# P08_eMMC.net
KiCad netlist of a schematic drawn in Altium Designer
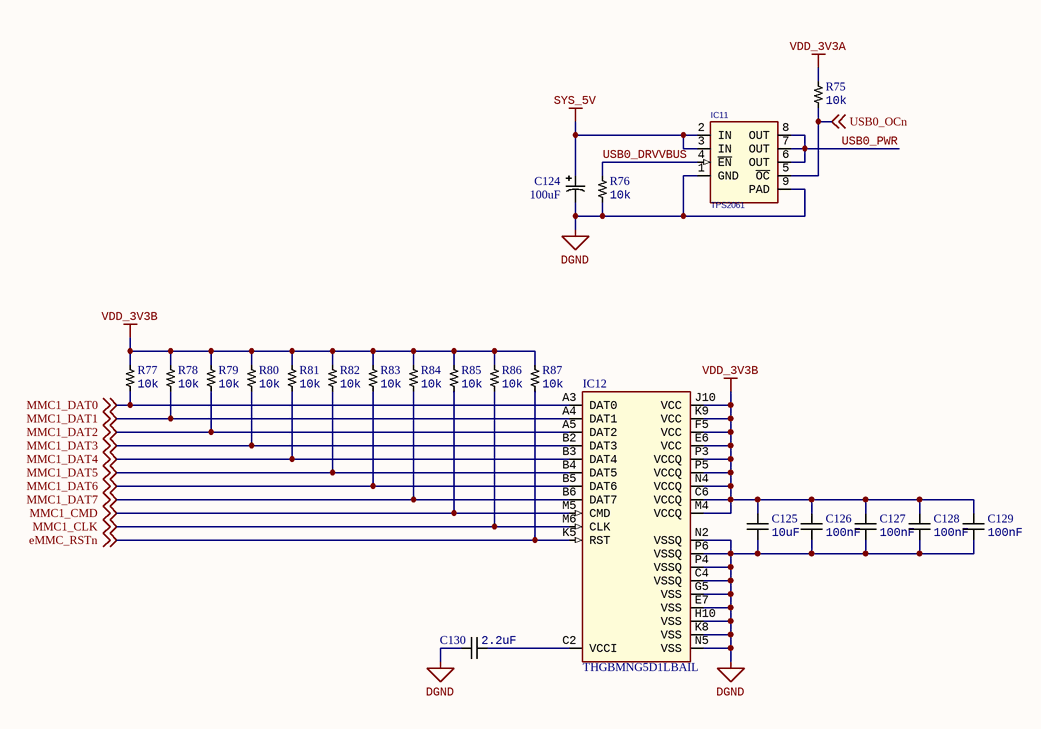
[diagram p0: P08_eMMC.SchDoc]

(export (version "E")
  (design (tool "Eeschema 10.0.6"))
  (components
    (comp (ref "C124")
      (value "EEE-0JA101SP")
      (footprint "Orient:CAP6.6x6.6")
      (description "POL CAP 100uF SMD")
      (fields
        (field (name "MANUFACTURER") "Panasonic")
        (field (name "TOLERANCE") "20%")
        (field (name "CAPACITANCE") "100uF")
      )
      (libsource (lib "Orient") (part "CAP_POL_100uF"))
    )
    (comp (ref "C125")
      (value "C2012X6S1A106K085AC")
      (footprint "Orient:CAP0805")
      (description "MLCC 10uF 0805 SMD")
      (fields
        (field (name "MANUFACTURER") "TDK")
        (field (name "CAPACITANCE") "10uF")
        (field (name "TOLERANCE") "10%")
      )
      (libsource (lib "Orient") (part "CAP_10uF"))
    )
    (comp (ref "C126")
      (value "C0402C104K4RACTU")
      (footprint "Orient:CAP0402")
      (description "MLCC 100nF 0402 SMD")
      (fields
        (field (name "MANUFACTURER") "KEMET")
        (field (name "TOLERANCE") "10%")
        (field (name "CAPACITANCE") "100nF")
      )
      (libsource (lib "Orient") (part "CAP_100nF"))
    )
    (comp (ref "C127")
      (value "C0402C104K4RACTU")
      (footprint "Orient:CAP0402")
      (description "MLCC 100nF 0402 SMD")
      (fields
        (field (name "MANUFACTURER") "KEMET")
        (field (name "TOLERANCE") "10%")
        (field (name "CAPACITANCE") "100nF")
      )
      (libsource (lib "Orient") (part "CAP_100nF"))
    )
    (comp (ref "C128")
      (value "C0402C104K4RACTU")
      (footprint "Orient:CAP0402")
      (description "MLCC 100nF 0402 SMD")
      (fields
        (field (name "MANUFACTURER") "KEMET")
        (field (name "TOLERANCE") "10%")
        (field (name "CAPACITANCE") "100nF")
      )
      (libsource (lib "Orient") (part "CAP_100nF"))
    )
    (comp (ref "C129")
      (value "C0402C104K4RACTU")
      (footprint "Orient:CAP0402")
      (description "MLCC 100nF 0402 SMD")
      (fields
        (field (name "MANUFACTURER") "KEMET")
        (field (name "TOLERANCE") "10%")
        (field (name "CAPACITANCE") "100nF")
      )
      (libsource (lib "Orient") (part "CAP_100nF"))
    )
    (comp (ref "C130")
      (value "C1005X5R0J225K050BC")
      (footprint "Orient:CAP0402")
      (description "MLCC 2.2uF 0402 SMD")
      (fields
        (field (name "MANUFACTURER") "TDK")
        (field (name "TOLERANCE") "10%")
        (field (name "CAPACITANCE") "2.2uF")
      )
      (libsource (lib "Orient") (part "CAP_2.2uF"))
    )
    (comp (ref "IC11")
      (value "TPS2061")
      (footprint "Orient:HVSSOP-8")
      (description "IC 1.5A PWR DIST SWITCH 8-SOIC")
      (fields
        (field (name "MANUFACTURER") "Texas Instruments")
        (field (name "MANUFACTURER PART NUMBER") "TPS2051BDGNR")
      )
      (libsource (lib "Orient") (part "TPS2061"))
    )
    (comp (ref "IC12")
      (value "THGBMNG5D1LBAIL")
      (footprint "Orient:WFBGA-153")
      (description "Flash Card 4G-byte 3.3V MultiMedia Card 153-Pin WFBGA")
      (fields
        (field (name "MANUFACTURER") "Micron Technology")
        (field (name "MANUFACTURER PART NUMBER") "MTFC2GMVEA-0M WT")
      )
      (libsource (lib "Orient") (part "IC_eMMC"))
    )
    (comp (ref "R75")
      (value "RC0402FR-0710KL")
      (footprint "Orient:RES0402")
      (description "Resistor 10kOhm 0402 SMD")
      (fields
        (field (name "MANUFACTURER") "Yageo")
        (field (name "TOLERANCE") "1%")
        (field (name "RESISTANCE") "10k")
      )
      (libsource (lib "Orient") (part "RES_10k"))
    )
    (comp (ref "R76")
      (value "RC0402FR-0710KL")
      (footprint "Orient:RES0402")
      (description "Resistor 10kOhm 0402 SMD")
      (fields
        (field (name "MANUFACTURER") "Yageo")
        (field (name "TOLERANCE") "1%")
        (field (name "RESISTANCE") "10k")
      )
      (libsource (lib "Orient") (part "RES_10k"))
    )
    (comp (ref "R77")
      (value "RC0402FR-0710KL")
      (footprint "Orient:RES0402")
      (description "Resistor 10kOhm 0402 SMD")
      (fields
        (field (name "MANUFACTURER") "Yageo")
        (field (name "TOLERANCE") "1%")
        (field (name "RESISTANCE") "10k")
      )
      (libsource (lib "Orient") (part "RES_10k"))
    )
    (comp (ref "R78")
      (value "RC0402FR-0710KL")
      (footprint "Orient:RES0402")
      (description "Resistor 10kOhm 0402 SMD")
      (fields
        (field (name "MANUFACTURER") "Yageo")
        (field (name "TOLERANCE") "1%")
        (field (name "RESISTANCE") "10k")
      )
      (libsource (lib "Orient") (part "RES_10k"))
    )
    (comp (ref "R79")
      (value "RC0402FR-0710KL")
      (footprint "Orient:RES0402")
      (description "Resistor 10kOhm 0402 SMD")
      (fields
        (field (name "MANUFACTURER") "Yageo")
        (field (name "TOLERANCE") "1%")
        (field (name "RESISTANCE") "10k")
      )
      (libsource (lib "Orient") (part "RES_10k"))
    )
    (comp (ref "R80")
      (value "RC0402FR-0710KL")
      (footprint "Orient:RES0402")
      (description "Resistor 10kOhm 0402 SMD")
      (fields
        (field (name "MANUFACTURER") "Yageo")
        (field (name "TOLERANCE") "1%")
        (field (name "RESISTANCE") "10k")
      )
      (libsource (lib "Orient") (part "RES_10k"))
    )
    (comp (ref "R81")
      (value "RC0402FR-0710KL")
      (footprint "Orient:RES0402")
      (description "Resistor 10kOhm 0402 SMD")
      (fields
        (field (name "MANUFACTURER") "Yageo")
        (field (name "TOLERANCE") "1%")
        (field (name "RESISTANCE") "10k")
      )
      (libsource (lib "Orient") (part "RES_10k"))
    )
    (comp (ref "R82")
      (value "RC0402FR-0710KL")
      (footprint "Orient:RES0402")
      (description "Resistor 10kOhm 0402 SMD")
      (fields
        (field (name "MANUFACTURER") "Yageo")
        (field (name "TOLERANCE") "1%")
        (field (name "RESISTANCE") "10k")
      )
      (libsource (lib "Orient") (part "RES_10k"))
    )
    (comp (ref "R83")
      (value "RC0402FR-0710KL")
      (footprint "Orient:RES0402")
      (description "Resistor 10kOhm 0402 SMD")
      (fields
        (field (name "MANUFACTURER") "Yageo")
        (field (name "TOLERANCE") "1%")
        (field (name "RESISTANCE") "10k")
      )
      (libsource (lib "Orient") (part "RES_10k"))
    )
    (comp (ref "R84")
      (value "RC0402FR-0710KL")
      (footprint "Orient:RES0402")
      (description "Resistor 10kOhm 0402 SMD")
      (fields
        (field (name "MANUFACTURER") "Yageo")
        (field (name "TOLERANCE") "1%")
        (field (name "RESISTANCE") "10k")
      )
      (libsource (lib "Orient") (part "RES_10k"))
    )
    (comp (ref "R85")
      (value "RC0402FR-0710KL")
      (footprint "Orient:RES0402")
      (description "Resistor 10kOhm 0402 SMD")
      (fields
        (field (name "MANUFACTURER") "Yageo")
        (field (name "TOLERANCE") "1%")
        (field (name "RESISTANCE") "10k")
      )
      (libsource (lib "Orient") (part "RES_10k"))
    )
    (comp (ref "R86")
      (value "RC0402FR-0710KL")
      (footprint "Orient:RES0402")
      (description "Resistor 10kOhm 0402 SMD")
      (fields
        (field (name "MANUFACTURER") "Yageo")
        (field (name "TOLERANCE") "1%")
        (field (name "RESISTANCE") "10k")
      )
      (libsource (lib "Orient") (part "RES_10k"))
    )
    (comp (ref "R87")
      (value "RC0402FR-0710KL")
      (footprint "Orient:RES0402")
      (description "Resistor 10kOhm 0402 SMD")
      (fields
        (field (name "MANUFACTURER") "Yageo")
        (field (name "TOLERANCE") "1%")
        (field (name "RESISTANCE") "10k")
      )
      (libsource (lib "Orient") (part "RES_10k"))
    )
  )
  (nets
    (net (code "1") (name "/USB0_DRVVBUS") (class "Default")
      (node (ref "IC11") (pin "4") (pinfunction "~{EN}_4") (pintype "input"))
      (node (ref "R76") (pin "1") (pintype "passive"))
    )
    (net (code "2") (name "/USB0_PWR") (class "Default")
      (node (ref "IC11") (pin "6") (pinfunction "OUT_6") (pintype "power_in"))
      (node (ref "IC11") (pin "7") (pinfunction "OUT_7") (pintype "power_in"))
      (node (ref "IC11") (pin "8") (pinfunction "OUT_8") (pintype "power_in"))
    )
    (net (code "3") (name "DGND") (class "Default")
      (node (ref "C124") (pin "2") (pinfunction "C_2") (pintype "passive"))
      (node (ref "C125") (pin "1") (pintype "passive"))
      (node (ref "C126") (pin "2") (pintype "passive"))
      (node (ref "C127") (pin "2") (pintype "passive"))
      (node (ref "C128") (pin "2") (pintype "passive"))
      (node (ref "C129") (pin "2") (pintype "passive"))
      (node (ref "C130") (pin "2") (pintype "passive"))
      (node (ref "IC11") (pin "1") (pinfunction "GND_1") (pintype "power_in"))
      (node (ref "IC11") (pin "9") (pinfunction "PAD_9") (pintype "passive"))
      (node (ref "IC12") (pin "C4") (pinfunction "VSSQ_C4") (pintype "power_in"))
      (node (ref "IC12") (pin "E7") (pinfunction "VSS_E7") (pintype "power_in"))
      (node (ref "IC12") (pin "G5") (pinfunction "VSS_G5") (pintype "power_in"))
      (node (ref "IC12") (pin "H10") (pinfunction "VSS_H10") (pintype "power_in"))
      (node (ref "IC12") (pin "K8") (pinfunction "VSS_K8") (pintype "power_in"))
      (node (ref "IC12") (pin "N2") (pinfunction "VSSQ_N2") (pintype "power_in"))
      (node (ref "IC12") (pin "N5") (pinfunction "VSS_N5") (pintype "power_in"))
      (node (ref "IC12") (pin "P4") (pinfunction "VSSQ_P4") (pintype "power_in"))
      (node (ref "IC12") (pin "P6") (pinfunction "VSSQ_P6") (pintype "power_in"))
      (node (ref "R76") (pin "2") (pintype "passive"))
    )
    (net (code "4") (name "MMC1_CLK") (class "Default")
      (node (ref "IC12") (pin "M6") (pinfunction "CLK_M6") (pintype "input"))
      (node (ref "R86") (pin "1") (pintype "passive"))
    )
    (net (code "5") (name "MMC1_CMD") (class "Default")
      (node (ref "IC12") (pin "M5") (pinfunction "CMD_M5") (pintype "input"))
      (node (ref "R85") (pin "1") (pintype "passive"))
    )
    (net (code "6") (name "MMC1_DAT0") (class "Default")
      (node (ref "IC12") (pin "A3") (pinfunction "DAT0_A3") (pintype "bidirectional"))
      (node (ref "R77") (pin "1") (pintype "passive"))
    )
    (net (code "7") (name "MMC1_DAT1") (class "Default")
      (node (ref "IC12") (pin "A4") (pinfunction "DAT1_A4") (pintype "bidirectional"))
      (node (ref "R78") (pin "1") (pintype "passive"))
    )
    (net (code "8") (name "MMC1_DAT2") (class "Default")
      (node (ref "IC12") (pin "A5") (pinfunction "DAT2_A5") (pintype "bidirectional"))
      (node (ref "R79") (pin "1") (pintype "passive"))
    )
    (net (code "9") (name "MMC1_DAT3") (class "Default")
      (node (ref "IC12") (pin "B2") (pinfunction "DAT3_B2") (pintype "bidirectional"))
      (node (ref "R80") (pin "1") (pintype "passive"))
    )
    (net (code "10") (name "MMC1_DAT4") (class "Default")
      (node (ref "IC12") (pin "B3") (pinfunction "DAT4_B3") (pintype "bidirectional"))
      (node (ref "R81") (pin "1") (pintype "passive"))
    )
    (net (code "11") (name "MMC1_DAT5") (class "Default")
      (node (ref "IC12") (pin "B4") (pinfunction "DAT5_B4") (pintype "bidirectional"))
      (node (ref "R82") (pin "1") (pintype "passive"))
    )
    (net (code "12") (name "MMC1_DAT6") (class "Default")
      (node (ref "IC12") (pin "B5") (pinfunction "DAT6_B5") (pintype "bidirectional"))
      (node (ref "R83") (pin "1") (pintype "passive"))
    )
    (net (code "13") (name "MMC1_DAT7") (class "Default")
      (node (ref "IC12") (pin "B6") (pinfunction "DAT7_B6") (pintype "bidirectional"))
      (node (ref "R84") (pin "1") (pintype "passive"))
    )
    (net (code "14") (name "Net-(IC12-VCCI)") (class "Default")
      (node (ref "C130") (pin "1") (pintype "passive"))
      (node (ref "IC12") (pin "C2") (pinfunction "VCCI_C2") (pintype "power_in"))
    )
    (net (code "15") (name "SYS_5V") (class "Default")
      (node (ref "C124") (pin "1") (pinfunction "A_1") (pintype "passive"))
      (node (ref "IC11") (pin "2") (pinfunction "IN_2") (pintype "power_in"))
      (node (ref "IC11") (pin "3") (pinfunction "IN_3") (pintype "power_in"))
    )
    (net (code "16") (name "USB0_OCn") (class "Default")
      (node (ref "IC11") (pin "5") (pinfunction "~{OC}_5") (pintype "passive"))
      (node (ref "R75") (pin "2") (pintype "passive"))
    )
    (net (code "17") (name "VDD_3V3A") (class "Default") (node (ref "R75") (pin "1") (pintype "passive")))
    (net (code "18") (name "VDD_3V3B") (class "Default")
      (node (ref "C125") (pin "2") (pintype "passive"))
      (node (ref "C126") (pin "1") (pintype "passive"))
      (node (ref "C127") (pin "1") (pintype "passive"))
      (node (ref "C128") (pin "1") (pintype "passive"))
      (node (ref "C129") (pin "1") (pintype "passive"))
      (node (ref "IC12") (pin "C6") (pinfunction "VCCQ_C6") (pintype "power_in"))
      (node (ref "IC12") (pin "E6") (pinfunction "VCC_E6") (pintype "power_in"))
      (node (ref "IC12") (pin "F5") (pinfunction "VCC_F5") (pintype "power_in"))
      (node (ref "IC12") (pin "J10") (pinfunction "VCC_J10") (pintype "power_in"))
      (node (ref "IC12") (pin "K9") (pinfunction "VCC_K9") (pintype "power_in"))
      (node (ref "IC12") (pin "M4") (pinfunction "VCCQ_M4") (pintype "power_in"))
      (node (ref "IC12") (pin "N4") (pinfunction "VCCQ_N4") (pintype "power_in"))
      (node (ref "IC12") (pin "P3") (pinfunction "VCCQ_P3") (pintype "power_in"))
      (node (ref "IC12") (pin "P5") (pinfunction "VCCQ_P5") (pintype "power_in"))
      (node (ref "R77") (pin "2") (pintype "passive"))
      (node (ref "R78") (pin "2") (pintype "passive"))
      (node (ref "R79") (pin "2") (pintype "passive"))
      (node (ref "R80") (pin "2") (pintype "passive"))
      (node (ref "R81") (pin "2") (pintype "passive"))
      (node (ref "R82") (pin "2") (pintype "passive"))
      (node (ref "R83") (pin "2") (pintype "passive"))
      (node (ref "R84") (pin "2") (pintype "passive"))
      (node (ref "R85") (pin "2") (pintype "passive"))
      (node (ref "R86") (pin "2") (pintype "passive"))
      (node (ref "R87") (pin "2") (pintype "passive"))
    )
    (net (code "19") (name "eMMC_RSTn") (class "Default")
      (node (ref "IC12") (pin "K5") (pinfunction "RST_K5") (pintype "input"))
      (node (ref "R87") (pin "1") (pintype "passive"))
    )
  )
)
